# ESP32_BLE.net
KiCad netlist of a schematic drawn in Altium Designer
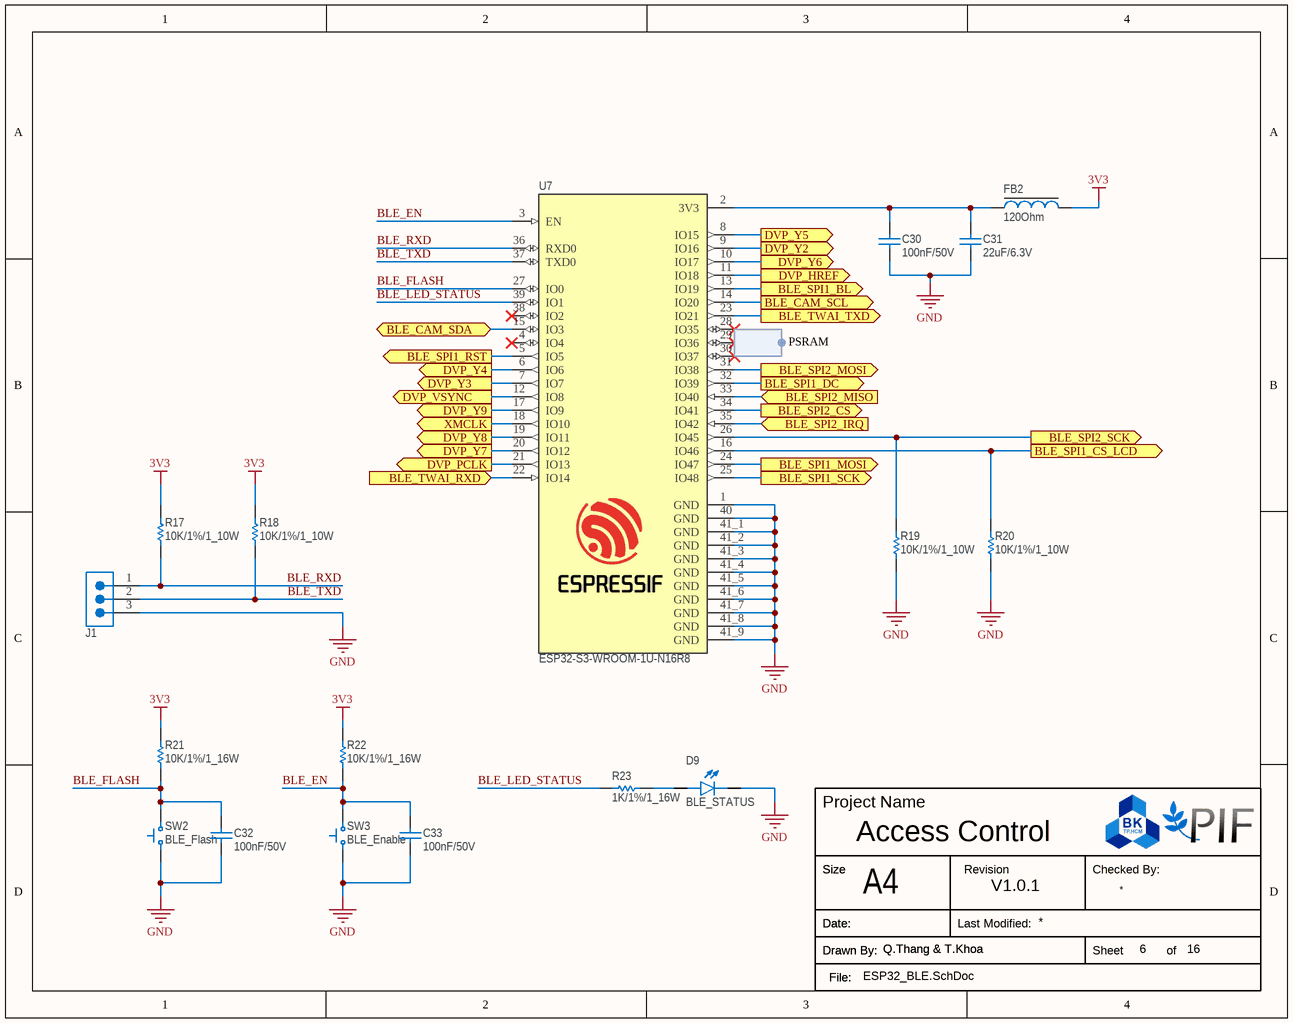
[diagram p0: ESP32_BLE.SchDoc]

(export (version "E")
  (design (tool "Eeschema 10.0.6"))
  (components
    (comp (ref "C30")
      (value "100nF/50V")
      (footprint "CAP_0805")
      (description "CAP, size 0805, 100nF, 50V")
      (fields (field (name "SUPPLY PART NUMBER") "Tụ Gốm 0805 100nF (0.1uF) 50V"))
      (libsource (lib "BluetoothTracking") (part "Ceramic_Cap_100nF_50V_0805"))
    )
    (comp (ref "C31")
      (value "22uF/6.3V")
      (footprint "CAP_0805")
      (description "CAP, size 0805, 22uF, 6.3V")
      (fields (field (name "SUPPLY PART NUMBER") "Tụ Gốm 0805 22uF 6.3V"))
      (libsource (lib "BluetoothTracking") (part "Ceramic_Cap_22uF_6.3V_0805"))
    )
    (comp (ref "C32")
      (value "100nF/50V")
      (footprint "CAP_0402")
      (description "CAP, size 0402, 100nF, 50V")
      (fields (field (name "SUPPLY PART NUMBER") "Tụ Gốm 0402 100nF (0.1uF) 50V"))
      (libsource (lib "BluetoothTracking") (part "Ceramic_Cap_100nF_50V_0402"))
    )
    (comp (ref "C33")
      (value "100nF/50V")
      (footprint "CAP_0402")
      (description "CAP, size 0402, 100nF, 50V")
      (fields (field (name "SUPPLY PART NUMBER") "Tụ Gốm 0402 100nF (0.1uF) 50V"))
      (libsource (lib "BluetoothTracking") (part "Ceramic_Cap_100nF_50V_0402"))
    )
    (comp (ref "D9")
      (value "BLE_STATUS")
      (footprint "LED_0603Y")
      (description "LED Yellow 0603")
      (fields (field (name "SUPPLY PART NUMBER") "LED Vàng 0603 Dán SMD Trong Suốt Harvatek"))
      (libsource (lib "BluetoothTracking") (part "LED_Yellow_0603"))
    )
    (comp (ref "FB2")
      (value "120Ohm")
      (footprint "Ferrite_Bead_0805")
      (description "Ferrite Bead, size 0805, 120Ohm, 2A")
      (fields (field (name "SUPPLY PART NUMBER") "CBW201209U121T Ferrite Beads 2A 120 Ohm 0805"))
      (libsource (lib "BluetoothTracking") (part "Ferrite_Bead_120Ohm_2A_0805"))
    )
    (comp (ref "J1")
      (value "2.54mm_2P")
      (footprint "Header_2.54mm_3P")
      (description "Hàng Rào Đực Đơn 2.54mm 40 Chân 1 Hàng Cao 11.2mm Xuyên Lỗ")
      (libsource (lib "BluetoothTracking") (part "Header_2.54mm_3P"))
    )
    (comp (ref "R17")
      (value "10K/1%/1_10W")
      (footprint "Resistor_0603")
      (description "Resistor 0603 10KOhm 1% 1_10W")
      (fields (field (name "SUPPLY PART NUMBER") "Điện Trở 10 KOhm 0603 1%"))
      (libsource (lib "BluetoothTracking") (part "Res_10K_0603_1%"))
    )
    (comp (ref "R18")
      (value "10K/1%/1_10W")
      (footprint "Resistor_0603")
      (description "Resistor 0603 10KOhm 1% 1_10W")
      (fields (field (name "SUPPLY PART NUMBER") "Điện Trở 10 KOhm 0603 1%"))
      (libsource (lib "BluetoothTracking") (part "Res_10K_0603_1%"))
    )
    (comp (ref "R19")
      (value "10K/1%/1_10W")
      (footprint "Resistor_0603")
      (description "Resistor 0603 10KOhm 1% 1_10W")
      (fields (field (name "SUPPLY PART NUMBER") "Điện Trở 10 KOhm 0603 1%"))
      (libsource (lib "BluetoothTracking") (part "Res_10K_0603_1%"))
    )
    (comp (ref "R20")
      (value "10K/1%/1_10W")
      (footprint "Resistor_0603")
      (description "Resistor 0603 10KOhm 1% 1_10W")
      (fields (field (name "SUPPLY PART NUMBER") "Điện Trở 10 KOhm 0603 1%"))
      (libsource (lib "BluetoothTracking") (part "Res_10K_0603_1%"))
    )
    (comp (ref "R21")
      (value "10K/1%/1_16W")
      (footprint "RESISTOR_0402")
      (description "Resistor 0402 10KOhm 1% 1_16W")
      (fields (field (name "SUPPLY PART NUMBER") "Điện Trở 10 KOhm 0402 1%"))
      (libsource (lib "BluetoothTracking") (part "Res_10K_0402_1%"))
    )
    (comp (ref "R22")
      (value "10K/1%/1_16W")
      (footprint "RESISTOR_0402")
      (description "Resistor 0402 10KOhm 1% 1_16W")
      (fields (field (name "SUPPLY PART NUMBER") "Điện Trở 10 KOhm 0402 1%"))
      (libsource (lib "BluetoothTracking") (part "Res_10K_0402_1%"))
    )
    (comp (ref "R23")
      (value "1K/1%/1_16W")
      (footprint "RESISTOR_0402")
      (description "Resistor 0402 1KOhm 1% 1_16W")
      (fields (field (name "SUPPLY PART NUMBER") "Điện Trở 1 KOhm 0402 1%"))
      (libsource (lib "BluetoothTracking") (part "Res_1K_0402_1%"))
    )
    (comp (ref "SW2")
      (value "BLE_Flash")
      (footprint "Button_3x4mm_SMD_2P")
      (fields (field (name "SUPPLY PART NUMBER") "Nút Nhấn 3x4mm Cao 2.5mm 2 Chân SMD"))
      (libsource (lib "BluetoothTracking") (part "Button_SMD_3x4mm_2P"))
    )
    (comp (ref "SW3")
      (value "BLE_Enable")
      (footprint "Button_3x4mm_SMD_2P")
      (fields (field (name "SUPPLY PART NUMBER") "Nút Nhấn 3x4mm Cao 2.5mm 2 Chân SMD"))
      (libsource (lib "BluetoothTracking") (part "Button_SMD_3x4mm_2P"))
    )
    (comp (ref "U7")
      (value "ESP32-S3-WROOM-1U-N16R8")
      (footprint "XCVR_ESP32-S3-WROOM-1U-N16R8")
      (fields (field (name "SUPPLY PART NUMBER") "ESP32-S3-WROOM-1U-N16R8 Thu Phát Wifi BLE ESP32 16MB"))
      (libsource (lib "BluetoothTracking") (part "ESP32-S3-WROOM-1U-N16R8"))
    )
  )
  (nets
    (net (code "1") (name "/BLE_CAM_SCL") (class "Default")
      (node (ref "U7") (pin "14") (pinfunction "IO20_14") (pintype "output"))
    )
    (net (code "2") (name "/BLE_CAM_SDA") (class "Default")
      (node (ref "U7") (pin "15") (pinfunction "IO3_15") (pintype "bidirectional"))
    )
    (net (code "3") (name "/BLE_EN") (class "Default")
      (node (ref "C33") (pin "2") (pinfunction "2_2") (pintype "passive"))
      (node (ref "R22") (pin "1") (pinfunction "1_1") (pintype "passive"))
      (node (ref "SW3") (pin "2") (pinfunction "2_2") (pintype "passive"))
      (node (ref "U7") (pin "3") (pinfunction "EN_3") (pintype "input"))
    )
    (net (code "4") (name "/BLE_FLASH") (class "Default")
      (node (ref "C32") (pin "2") (pinfunction "2_2") (pintype "passive"))
      (node (ref "R21") (pin "1") (pinfunction "1_1") (pintype "passive"))
      (node (ref "SW2") (pin "2") (pinfunction "2_2") (pintype "passive"))
      (node (ref "U7") (pin "27") (pinfunction "IO0_27") (pintype "bidirectional"))
    )
    (net (code "5") (name "/BLE_LED_STATUS") (class "Default")
      (node (ref "R23") (pin "1") (pinfunction "1_1") (pintype "passive"))
      (node (ref "U7") (pin "39") (pinfunction "IO1_39") (pintype "bidirectional"))
    )
    (net (code "6") (name "/BLE_RXD") (class "Default")
      (node (ref "J1") (pin "1") (pinfunction "1_1") (pintype "passive"))
      (node (ref "R17") (pin "1") (pinfunction "1_1") (pintype "passive"))
      (node (ref "U7") (pin "36") (pinfunction "RXD0_36") (pintype "bidirectional"))
    )
    (net (code "7") (name "/BLE_SPI1_BL") (class "Default")
      (node (ref "U7") (pin "13") (pinfunction "IO19_13") (pintype "output"))
    )
    (net (code "8") (name "/BLE_SPI1_CS_LCD") (class "Default")
      (node (ref "R20") (pin "2") (pinfunction "2_2") (pintype "passive"))
      (node (ref "U7") (pin "16") (pinfunction "IO46_16") (pintype "output"))
    )
    (net (code "9") (name "/BLE_SPI1_DC") (class "Default")
      (node (ref "U7") (pin "32") (pinfunction "IO39_32") (pintype "output"))
    )
    (net (code "10") (name "/BLE_SPI1_MOSI") (class "Default")
      (node (ref "U7") (pin "24") (pinfunction "IO47_24") (pintype "output"))
    )
    (net (code "11") (name "/BLE_SPI1_RST") (class "Default")
      (node (ref "U7") (pin "5") (pinfunction "IO5_5") (pintype "output"))
    )
    (net (code "12") (name "/BLE_SPI1_SCK") (class "Default")
      (node (ref "U7") (pin "25") (pinfunction "IO48_25") (pintype "output"))
    )
    (net (code "13") (name "/BLE_SPI2_CS") (class "Default")
      (node (ref "U7") (pin "34") (pinfunction "IO41_34") (pintype "output"))
    )
    (net (code "14") (name "/BLE_SPI2_IRQ") (class "Default")
      (node (ref "U7") (pin "35") (pinfunction "IO42_35") (pintype "input"))
    )
    (net (code "15") (name "/BLE_SPI2_MISO") (class "Default")
      (node (ref "U7") (pin "33") (pinfunction "IO40_33") (pintype "input"))
    )
    (net (code "16") (name "/BLE_SPI2_MOSI") (class "Default")
      (node (ref "U7") (pin "31") (pinfunction "IO38_31") (pintype "output"))
    )
    (net (code "17") (name "/BLE_SPI2_SCK") (class "Default")
      (node (ref "R19") (pin "2") (pinfunction "2_2") (pintype "passive"))
      (node (ref "U7") (pin "26") (pinfunction "IO45_26") (pintype "output"))
    )
    (net (code "18") (name "/BLE_TWAI_RXD") (class "Default")
      (node (ref "U7") (pin "22") (pinfunction "IO14_22") (pintype "input"))
    )
    (net (code "19") (name "/BLE_TWAI_TXD") (class "Default")
      (node (ref "U7") (pin "23") (pinfunction "IO21_23") (pintype "output"))
    )
    (net (code "20") (name "/BLE_TXD") (class "Default")
      (node (ref "J1") (pin "2") (pinfunction "2_2") (pintype "passive"))
      (node (ref "R18") (pin "1") (pinfunction "1_1") (pintype "passive"))
      (node (ref "U7") (pin "37") (pinfunction "TXD0_37") (pintype "bidirectional"))
    )
    (net (code "21") (name "/DVP_HREF") (class "Default")
      (node (ref "U7") (pin "11") (pinfunction "IO18_11") (pintype "output"))
    )
    (net (code "22") (name "/DVP_PCLK") (class "Default")
      (node (ref "U7") (pin "21") (pinfunction "IO13_21") (pintype "output"))
    )
    (net (code "23") (name "/DVP_VSYNC") (class "Default")
      (node (ref "U7") (pin "12") (pinfunction "IO8_12") (pintype "output"))
    )
    (net (code "24") (name "/DVP_Y2") (class "Default")
      (node (ref "U7") (pin "9") (pinfunction "IO16_9") (pintype "output"))
    )
    (net (code "25") (name "/DVP_Y3") (class "Default")
      (node (ref "U7") (pin "7") (pinfunction "IO7_7") (pintype "output"))
    )
    (net (code "26") (name "/DVP_Y4") (class "Default")
      (node (ref "U7") (pin "6") (pinfunction "IO6_6") (pintype "output"))
    )
    (net (code "27") (name "/DVP_Y5") (class "Default")
      (node (ref "U7") (pin "8") (pinfunction "IO15_8") (pintype "output"))
    )
    (net (code "28") (name "/DVP_Y6") (class "Default")
      (node (ref "U7") (pin "10") (pinfunction "IO17_10") (pintype "output"))
    )
    (net (code "29") (name "/DVP_Y7") (class "Default")
      (node (ref "U7") (pin "20") (pinfunction "IO12_20") (pintype "output"))
    )
    (net (code "30") (name "/DVP_Y8") (class "Default")
      (node (ref "U7") (pin "19") (pinfunction "IO11_19") (pintype "output"))
    )
    (net (code "31") (name "/DVP_Y9") (class "Default")
      (node (ref "U7") (pin "17") (pinfunction "IO9_17") (pintype "output"))
    )
    (net (code "32") (name "/XMCLK") (class "Default")
      (node (ref "U7") (pin "18") (pinfunction "IO10_18") (pintype "output"))
    )
    (net (code "33") (name "3V3") (class "Default")
      (node (ref "FB2") (pin "2") (pinfunction "2_2") (pintype "passive"))
      (node (ref "R17") (pin "2") (pinfunction "2_2") (pintype "passive"))
      (node (ref "R18") (pin "2") (pinfunction "2_2") (pintype "passive"))
      (node (ref "R21") (pin "2") (pinfunction "2_2") (pintype "passive"))
      (node (ref "R22") (pin "2") (pinfunction "2_2") (pintype "passive"))
    )
    (net (code "34") (name "GND") (class "Default")
      (node (ref "C30") (pin "1") (pinfunction "1_1") (pintype "passive"))
      (node (ref "C31") (pin "1") (pinfunction "1_1") (pintype "passive"))
      (node (ref "C32") (pin "1") (pinfunction "1_1") (pintype "passive"))
      (node (ref "C33") (pin "1") (pinfunction "1_1") (pintype "passive"))
      (node (ref "D9") (pin "C") (pinfunction "C_C") (pintype "passive"))
      (node (ref "J1") (pin "3") (pinfunction "3_3") (pintype "passive"))
      (node (ref "R19") (pin "1") (pinfunction "1_1") (pintype "passive"))
      (node (ref "R20") (pin "1") (pinfunction "1_1") (pintype "passive"))
      (node (ref "SW2") (pin "1") (pinfunction "1_1") (pintype "passive"))
      (node (ref "SW3") (pin "1") (pinfunction "1_1") (pintype "passive"))
      (node (ref "U7") (pin "1") (pinfunction "GND_1") (pintype "power_in"))
      (node (ref "U7") (pin "40") (pinfunction "GND_40") (pintype "power_in"))
      (node (ref "U7") (pin "41_1") (pinfunction "GND_41_1") (pintype "power_in"))
      (node (ref "U7") (pin "41_2") (pinfunction "GND_41_2") (pintype "power_in"))
      (node (ref "U7") (pin "41_3") (pinfunction "GND_41_3") (pintype "power_in"))
      (node (ref "U7") (pin "41_4") (pinfunction "GND_41_4") (pintype "power_in"))
      (node (ref "U7") (pin "41_5") (pinfunction "GND_41_5") (pintype "power_in"))
      (node (ref "U7") (pin "41_6") (pinfunction "GND_41_6") (pintype "power_in"))
      (node (ref "U7") (pin "41_7") (pinfunction "GND_41_7") (pintype "power_in"))
      (node (ref "U7") (pin "41_8") (pinfunction "GND_41_8") (pintype "power_in"))
      (node (ref "U7") (pin "41_9") (pinfunction "GND_41_9") (pintype "power_in"))
    )
    (net (code "35") (name "Net-(D9-PadA)") (class "Default")
      (node (ref "D9") (pin "A") (pinfunction "A_A") (pintype "passive"))
      (node (ref "R23") (pin "2") (pinfunction "2_2") (pintype "passive"))
    )
    (net (code "36") (name "Net-(U7-3V3)") (class "Default")
      (node (ref "C30") (pin "2") (pinfunction "2_2") (pintype "passive"))
      (node (ref "C31") (pin "2") (pinfunction "2_2") (pintype "passive"))
      (node (ref "FB2") (pin "1") (pinfunction "1_1") (pintype "passive"))
      (node (ref "U7") (pin "2") (pinfunction "3V3_2") (pintype "power_in"))
    )
    (net (code "37") (name "unconnected-(U7-IO2-Pad38)") (class "Default")
      (node (ref "U7") (pin "38") (pinfunction "IO2_38") (pintype "bidirectional+no_connect"))
    )
    (net (code "38") (name "unconnected-(U7-IO4-Pad4)") (class "Default")
      (node (ref "U7") (pin "4") (pinfunction "IO4_4") (pintype "bidirectional+no_connect"))
    )
    (net (code "39") (name "unconnected-(U7-IO35-Pad28)") (class "Default")
      (node (ref "U7") (pin "28") (pinfunction "IO35_28") (pintype "bidirectional+no_connect"))
    )
    (net (code "40") (name "unconnected-(U7-IO36-Pad29)") (class "Default")
      (node (ref "U7") (pin "29") (pinfunction "IO36_29") (pintype "bidirectional+no_connect"))
    )
    (net (code "41") (name "unconnected-(U7-IO37-Pad30)") (class "Default")
      (node (ref "U7") (pin "30") (pinfunction "IO37_30") (pintype "bidirectional+no_connect"))
    )
  )
)
